# Roaster_Breakout.net
KiCad netlist of a schematic drawn in EAGLE
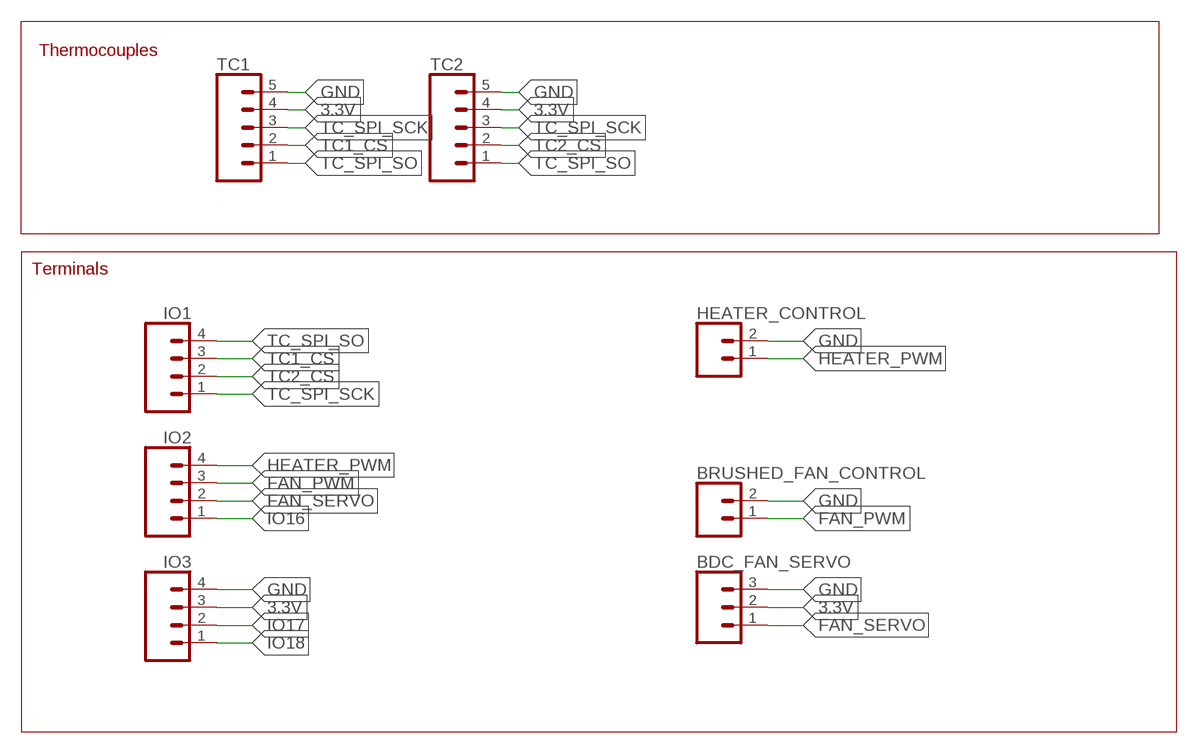
[diagram p0: schematic, sheet 1]

(export (version "E")
  (design (tool "Eeschema 10.0.6"))
  (components
    (comp (ref "BDC_FAN_SERVO")
      (value "CONN_03LONGPADS")
      (footprint "eagle-import:1X03_LONGPADS")
      (libsource (lib "eagle-import") (part "CONN_03LONGPADS"))
    )
    (comp (ref "BRUSHED_FAN_CONTROL")
      (value "CONN_02PTH3")
      (footprint "eagle-import:1X02_LONGPADS")
      (libsource (lib "eagle-import") (part "CONN_02PTH3"))
    )
    (comp (ref "HEATER_CONTROL")
      (value "CONN_02PTH3")
      (footprint "eagle-import:1X02_LONGPADS")
      (libsource (lib "eagle-import") (part "CONN_02PTH3"))
    )
    (comp (ref "IO1")
      (value "CONN_04LONGPADS")
      (footprint "eagle-import:1X04_LONGPADS")
      (libsource (lib "eagle-import") (part "CONN_04LONGPADS"))
    )
    (comp (ref "IO2")
      (value "CONN_04LONGPADS")
      (footprint "eagle-import:1X04_LONGPADS")
      (libsource (lib "eagle-import") (part "CONN_04LONGPADS"))
    )
    (comp (ref "IO3")
      (value "CONN_04LONGPADS")
      (footprint "eagle-import:1X04_LONGPADS")
      (libsource (lib "eagle-import") (part "CONN_04LONGPADS"))
    )
    (comp (ref "TC1")
      (value "CONN_05PTH_LONGPADS")
      (footprint "eagle-import:1X05_LONGPADS")
      (libsource (lib "eagle-import") (part "CONN_05PTH_LONGPADS"))
    )
    (comp (ref "TC2")
      (value "CONN_05PTH_LONGPADS")
      (footprint "eagle-import:1X05_LONGPADS")
      (libsource (lib "eagle-import") (part "CONN_05PTH_LONGPADS"))
    )
  )
  (nets
    (net (code "1") (name "3.3V") (class "Default")
      (node (ref "BDC_FAN_SERVO") (pin "2") (pinfunction "2_2") (pintype "passive"))
      (node (ref "IO3") (pin "3") (pinfunction "3_3") (pintype "passive"))
      (node (ref "TC1") (pin "4") (pinfunction "4_4") (pintype "passive"))
      (node (ref "TC2") (pin "4") (pinfunction "4_4") (pintype "passive"))
    )
    (net (code "2") (name "FAN_PWM") (class "Default")
      (node (ref "BRUSHED_FAN_CONTROL") (pin "1") (pinfunction "1_1") (pintype "passive"))
      (node (ref "IO2") (pin "3") (pinfunction "3_3") (pintype "passive"))
    )
    (net (code "3") (name "FAN_SERVO") (class "Default")
      (node (ref "BDC_FAN_SERVO") (pin "1") (pinfunction "1_1") (pintype "passive"))
      (node (ref "IO2") (pin "2") (pinfunction "2_2") (pintype "passive"))
    )
    (net (code "4") (name "GND") (class "Default")
      (node (ref "BDC_FAN_SERVO") (pin "3") (pinfunction "3_3") (pintype "passive"))
      (node (ref "BRUSHED_FAN_CONTROL") (pin "2") (pinfunction "2_2") (pintype "passive"))
      (node (ref "HEATER_CONTROL") (pin "2") (pinfunction "2_2") (pintype "passive"))
      (node (ref "IO3") (pin "4") (pinfunction "4_4") (pintype "passive"))
      (node (ref "TC1") (pin "5") (pinfunction "5_5") (pintype "passive"))
      (node (ref "TC2") (pin "5") (pinfunction "5_5") (pintype "passive"))
    )
    (net (code "5") (name "HEATER_PWM") (class "Default")
      (node (ref "HEATER_CONTROL") (pin "1") (pinfunction "1_1") (pintype "passive"))
      (node (ref "IO2") (pin "4") (pinfunction "4_4") (pintype "passive"))
    )
    (net (code "6") (name "IO16") (class "Default")
      (node (ref "IO2") (pin "1") (pinfunction "1_1") (pintype "passive"))
    )
    (net (code "7") (name "IO17") (class "Default")
      (node (ref "IO3") (pin "2") (pinfunction "2_2") (pintype "passive"))
    )
    (net (code "8") (name "IO18") (class "Default")
      (node (ref "IO3") (pin "1") (pinfunction "1_1") (pintype "passive"))
    )
    (net (code "9") (name "TC1_CS") (class "Default")
      (node (ref "IO1") (pin "3") (pinfunction "3_3") (pintype "passive"))
      (node (ref "TC1") (pin "2") (pinfunction "2_2") (pintype "passive"))
    )
    (net (code "10") (name "TC2_CS") (class "Default")
      (node (ref "IO1") (pin "2") (pinfunction "2_2") (pintype "passive"))
      (node (ref "TC2") (pin "2") (pinfunction "2_2") (pintype "passive"))
    )
    (net (code "11") (name "TC_SPI_SCK") (class "Default")
      (node (ref "IO1") (pin "1") (pinfunction "1_1") (pintype "passive"))
      (node (ref "TC1") (pin "3") (pinfunction "3_3") (pintype "passive"))
      (node (ref "TC2") (pin "3") (pinfunction "3_3") (pintype "passive"))
    )
    (net (code "12") (name "TC_SPI_SO") (class "Default")
      (node (ref "IO1") (pin "4") (pinfunction "4_4") (pintype "passive"))
      (node (ref "TC1") (pin "1") (pinfunction "1_1") (pintype "passive"))
      (node (ref "TC2") (pin "1") (pinfunction "1_1") (pintype "passive"))
    )
  )
)
